# Headers_Controller.net
KiCad netlist of a schematic drawn in Altium Designer
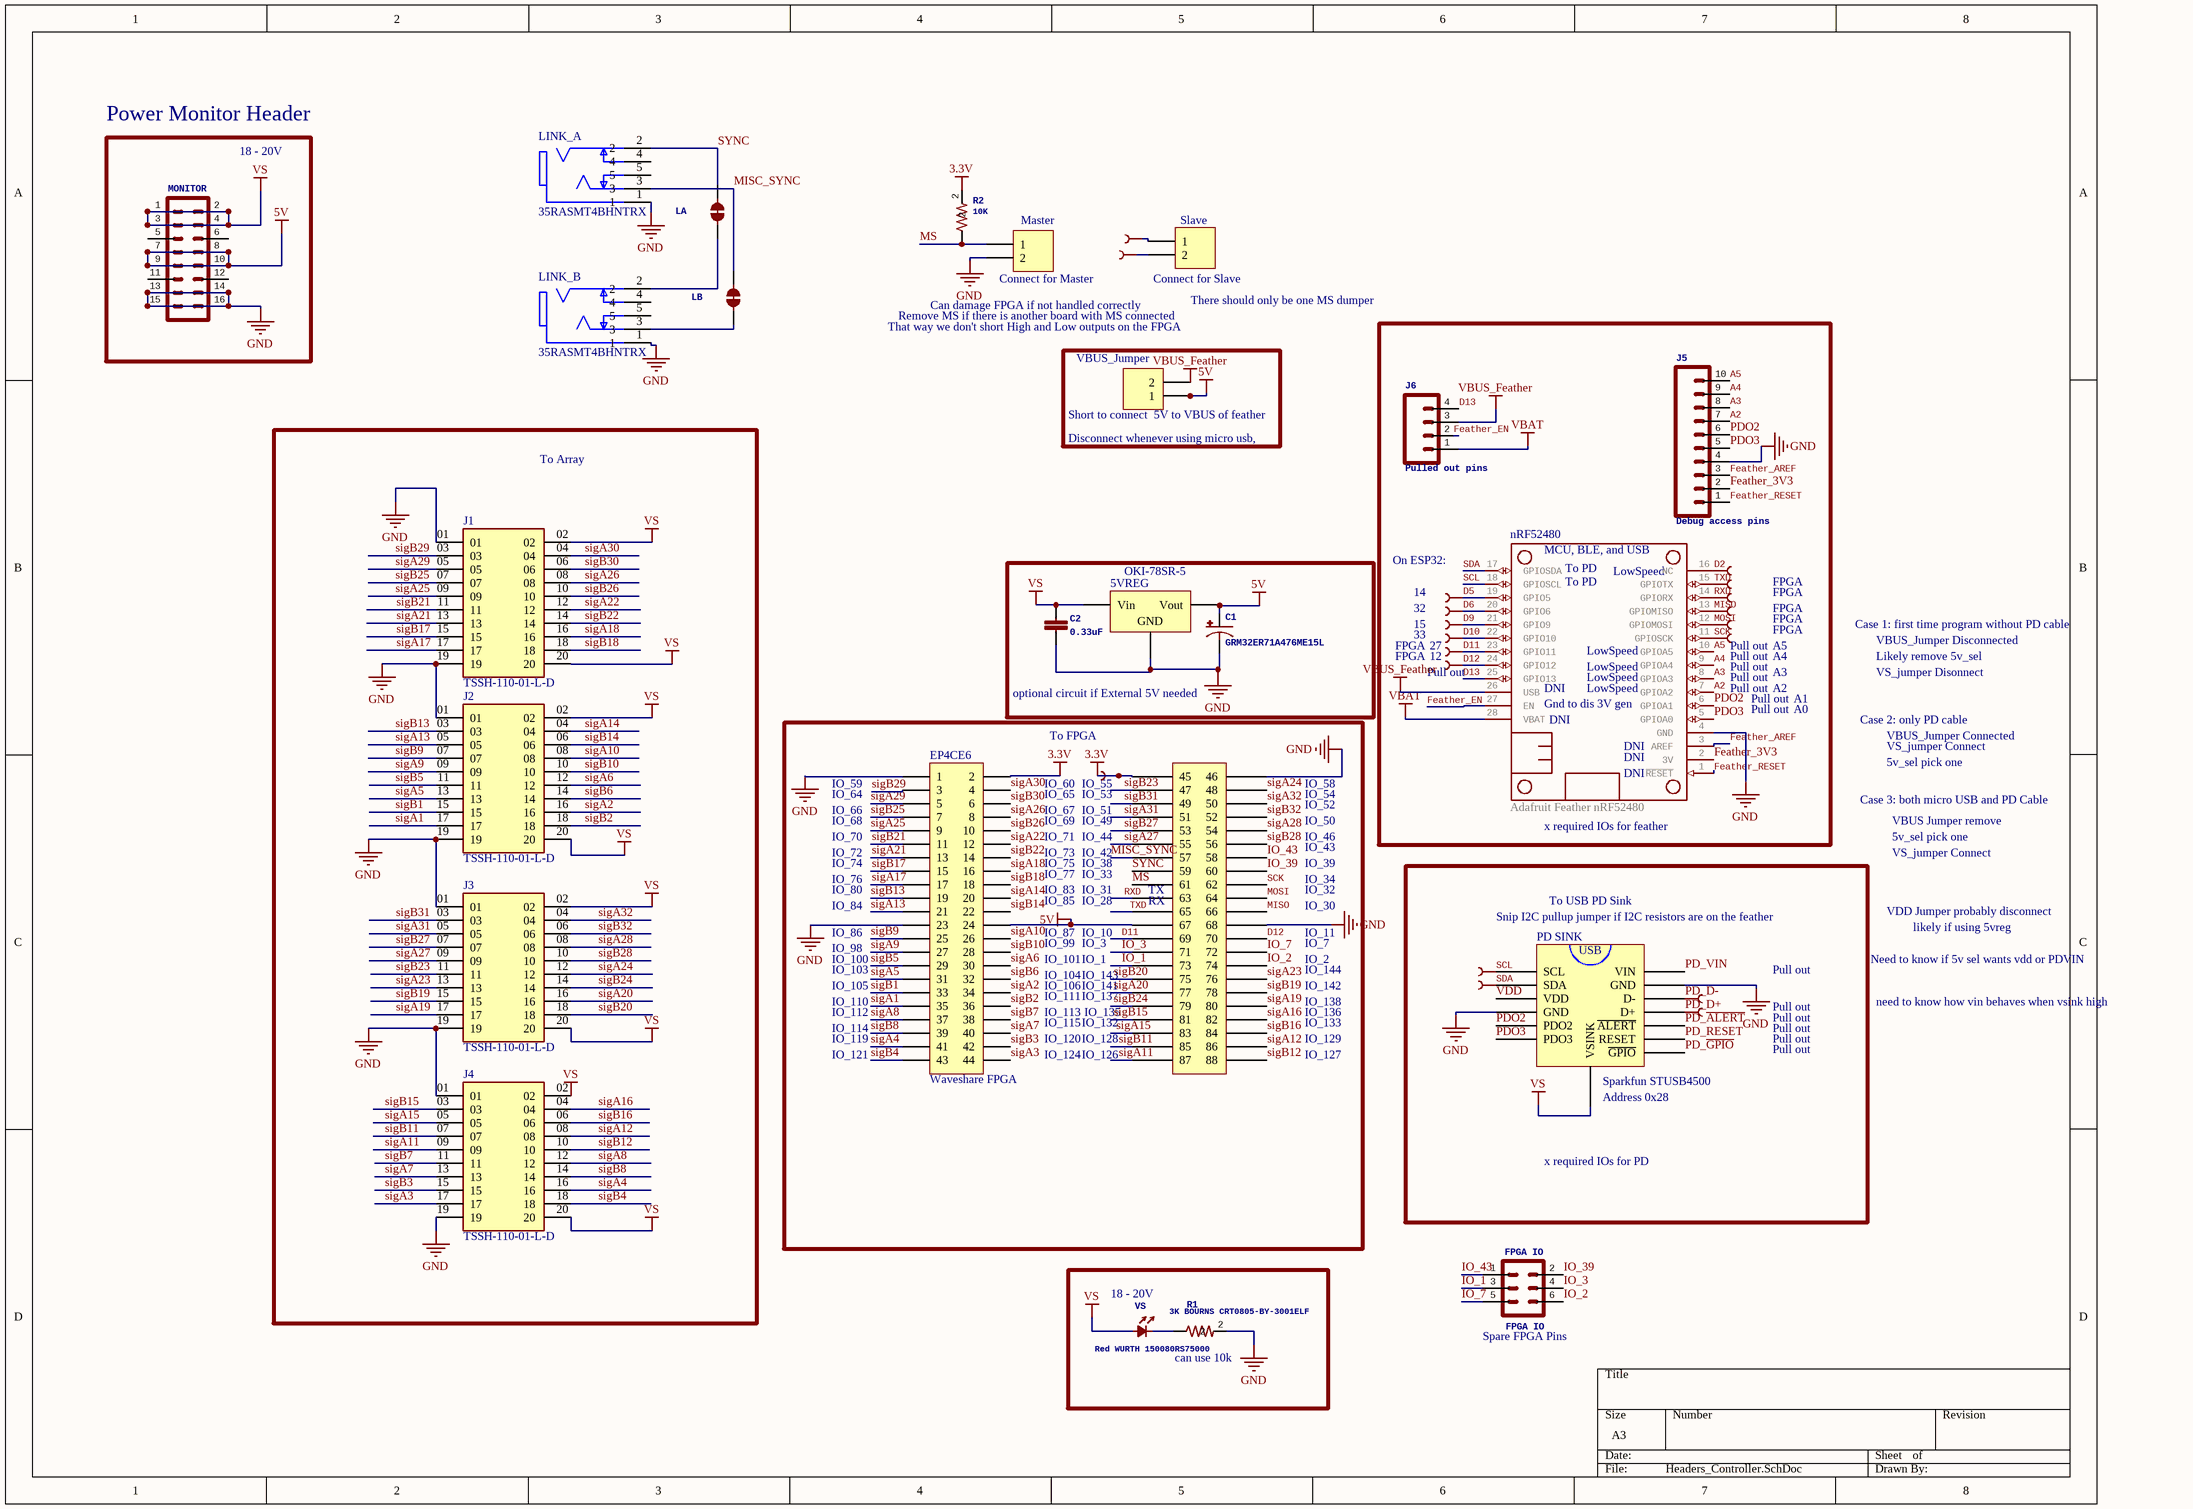
[diagram p0: Headers_Controller.SchDoc]

(export (version "E")
  (design (tool "Eeschema 10.0.6"))
  (components
    (comp (ref "3V3")
      (value "TEST-POINT3X5")
      (footprint "PAD.03X.05")
      (libsource (lib "SparkFun-Connectors") (part "TEST-POINT3X5"))
    )
    (comp (ref "5VREG")
      (value "OKI-78SR-5")
      (footprint "OOKA-78SR")
      (description "Voltage Regulator")
      (fields (field (name "PUBLISHER") "Altium Limited"))
      (libsource (lib "InteractLab") (part "Volt Reg"))
    )
    (comp (ref "C1")
      (value "GRM32ER71A476ME15L")
      (footprint "EIA6032-NOM")
      (libsource (lib "InteractLab") (part "CAP ELECTRO"))
    )
    (comp (ref "C2")
      (value "0.33uF")
      (footprint "CAP0805")
      (libsource (lib "InteractLab") (part "CAP CERAMIC"))
    )
    (comp (ref "D+")
      (value "TEST-POINT3X5")
      (footprint "PAD.03X.05")
      (libsource (lib "SparkFun-Connectors") (part "TEST-POINT3X5"))
    )
    (comp (ref "D-")
      (value "TEST-POINT3X5")
      (footprint "PAD.03X.05")
      (libsource (lib "SparkFun-Connectors") (part "TEST-POINT3X5"))
    )
    (comp (ref "D2")
      (value "TEST-POINT3X5")
      (footprint "PAD.03X.05")
      (libsource (lib "SparkFun-Connectors") (part "TEST-POINT3X5"))
    )
    (comp (ref "D5")
      (value "TEST-POINT3X5")
      (footprint "PAD.03X.05")
      (libsource (lib "SparkFun-Connectors") (part "TEST-POINT3X5"))
    )
    (comp (ref "D6")
      (value "TEST-POINT3X5")
      (footprint "PAD.03X.05")
      (libsource (lib "SparkFun-Connectors") (part "TEST-POINT3X5"))
    )
    (comp (ref "D9")
      (value "TEST-POINT3X5")
      (footprint "PAD.03X.05")
      (libsource (lib "SparkFun-Connectors") (part "TEST-POINT3X5"))
    )
    (comp (ref "D10")
      (value "TEST-POINT3X5")
      (footprint "PAD.03X.05")
      (libsource (lib "SparkFun-Connectors") (part "TEST-POINT3X5"))
    )
    (comp (ref "D11")
      (value "TEST-POINT3X5")
      (footprint "PAD.03X.05")
      (libsource (lib "SparkFun-Connectors") (part "TEST-POINT3X5"))
    )
    (comp (ref "D12")
      (value "TEST-POINT3X5")
      (footprint "PAD.03X.05")
      (libsource (lib "SparkFun-Connectors") (part "TEST-POINT3X5"))
    )
    (comp (ref "EP4CE6")
      (value "Waveshare FPGA")
      (footprint "EP4CE6 Waveshare FPGA")
      (fields (field (name "MF") "{'manufacturer': u'TE Connectivity'}") (field (name "MP") "7-534206-2"))
      (libsource (lib "InteractLab") (part "EP4CE6"))
    )
    (comp (ref "FPGA IO")
      (value "FPGA IO")
      (footprint "2X3")
      (libsource (lib "SparkFun-Connectors") (part "CONN_03X22X3_SILK_MALE_PTH"))
    )
    (comp (ref "J1")
      (value "TSSH-110-01-L-D")
      (footprint "InteractLab:SAMTEC_TSSH-110-01-L-D")
      (libsource (lib "InteractLab") (part "TSSH-110-01-L-D"))
    )
    (comp (ref "J2")
      (value "TSSH-110-01-L-D")
      (footprint "InteractLab:SAMTEC_TSSH-110-01-L-D")
      (libsource (lib "InteractLab") (part "TSSH-110-01-L-D"))
    )
    (comp (ref "J3")
      (value "TSSH-110-01-L-D")
      (footprint "InteractLab:SAMTEC_TSSH-110-01-L-D")
      (libsource (lib "InteractLab") (part "TSSH-110-01-L-D"))
    )
    (comp (ref "J4")
      (value "TSSH-110-01-L-D")
      (footprint "InteractLab:SAMTEC_TSSH-110-01-L-D")
      (libsource (lib "InteractLab") (part "TSSH-110-01-L-D"))
    )
    (comp (ref "J5")
      (value "Debug access pins")
      (footprint "1X10 _ LOCK - header")
      (libsource (lib "InteractLab") (part "CONN_10LOCK_1"))
    )
    (comp (ref "J6")
      (value "Pulled out pins")
      (footprint "1X04_LOCK - header")
      (description "Debug access pins")
      (libsource (lib "InteractLab") (part "CONN_04LOCK"))
    )
    (comp (ref "LA")
      (value "Normally closed trace jumper    This jumper has a trace between two pads so it's normally closed (NC). Use a razor knife to open the connection. For best results follow the IPC guidelines for cutting traces: Cutout at least 0.063 mm (0.005 in).  Remove all loose material to clean up the cut area.  Seal the cut with an approved epoxy.       Reapply solder to reclose the connection.")
      (footprint "SMT-JUMPER_2_NC_TRACE_SILK")
      (description "Optional disconnect")
      (libsource (lib "SparkFun-Jumpers") (part "JUMPER-SMT_2_NC_TRACE_SILK"))
    )
    (comp (ref "LB")
      (value "Normally closed trace jumper    This jumper has a trace between two pads so it's normally closed (NC). Use a razor knife to open the connection. For best results follow the IPC guidelines for cutting traces: Cutout at least 0.063 mm (0.005 in).  Remove all loose material to clean up the cut area.  Seal the cut with an approved epoxy.       Reapply solder to reclose the connection.")
      (footprint "SMT-JUMPER_2_NC_TRACE_SILK")
      (description "Optional disconnect")
      (libsource (lib "SparkFun-Jumpers") (part "JUMPER-SMT_2_NC_TRACE_SILK"))
    )
    (comp (ref "LINK_A")
      (value "35RASMT4BHNTRX")
      (footprint "SWITCHCRAFT_35RASMT4BHNTRX")
      (description "Sync port A")
      (fields (field (name "MF") "{'manufacturer': u'Switchcraft'}"))
      (libsource (lib "SnapEDA_Library") (part "35RASMT4BHNTRX"))
    )
    (comp (ref "LINK_B")
      (value "35RASMT4BHNTRX")
      (footprint "SWITCHCRAFT_35RASMT4BHNTRX")
      (description "Sync port B")
      (fields (field (name "MF") "{'manufacturer': u'Switchcraft'}"))
      (libsource (lib "SnapEDA_Library") (part "35RASMT4BHNTRX"))
    )
    (comp (ref "Master")
      (value "Connect for Master")
      (footprint "1X02_LOCK_")
      (fields (field (name "PUBLISHER") "Altium Limited"))
      (libsource (lib "") (part "Header 2_1"))
    )
    (comp (ref "MISO")
      (value "TEST-POINT3X5")
      (footprint "PAD.03X.05")
      (libsource (lib "SparkFun-Connectors") (part "TEST-POINT3X5"))
    )
    (comp (ref "MONITOR")
      (value "Access to power rails")
      (footprint "2X8")
      (libsource (lib "SparkFun-Connectors") (part "CONN_08X2_HEADER"))
    )
    (comp (ref "MOSI")
      (value "TEST-POINT3X5")
      (footprint "PAD.03X.05")
      (libsource (lib "SparkFun-Connectors") (part "TEST-POINT3X5"))
    )
    (comp (ref "nRF52480")
      (value "Adafruit Feather nRF52480")
      (footprint "Feather BLE nRF52480")
      (libsource (lib "InteractLab") (part "FEATHERWING_NODIM"))
    )
    (comp (ref "PD SINK")
      (value "Sparkfun STUSB4500")
      (footprint "Sparkfun STUSB4500")
      (description "Replace with purple board")
      (libsource (lib "InteractLab") (part "Sparkfun STUSB"))
    )
    (comp (ref "R1")
      (value "3K BOURNS CRT0805-BY-3001ELF")
      (footprint "RES-0805")
      (fields (field (name "MF") "Vishay") (field (name "MPN") "CRCW0603470RFKEA"))
      (libsource (lib "InteractLab") (part "RESISTOR"))
    )
    (comp (ref "R2")
      (value "10K")
      (footprint "RES-0805")
      (fields (field (name "MF") "Vishay") (field (name "MPN") "CRCW0603470RFKEA"))
      (libsource (lib "InteractLab") (part "RESISTOR"))
    )
    (comp (ref "RX")
      (value "TEST-POINT3X5")
      (footprint "PAD.03X.05")
      (libsource (lib "SparkFun-Connectors") (part "TEST-POINT3X5"))
    )
    (comp (ref "SCK")
      (value "TEST-POINT3X5")
      (footprint "PAD.03X.05")
      (libsource (lib "SparkFun-Connectors") (part "TEST-POINT3X5"))
    )
    (comp (ref "SCL")
      (value "TEST-POINT3X5")
      (footprint "PAD.03X.05")
      (libsource (lib "SparkFun-Connectors") (part "TEST-POINT3X5"))
    )
    (comp (ref "SDA")
      (value "TEST-POINT3X5")
      (footprint "PAD.03X.05")
      (libsource (lib "SparkFun-Connectors") (part "TEST-POINT3X5"))
    )
    (comp (ref "Slave")
      (value "Connect for Slave")
      (footprint "1X02_LOCK_")
      (description "Header, 2-Pin")
      (fields (field (name "PUBLISHER") "Altium Limited"))
      (libsource (lib "") (part "Header 2_1"))
    )
    (comp (ref "TP1")
      (value "TEST-POINT3X5")
      (footprint "PAD.03X.05")
      (libsource (lib "SparkFun-Connectors") (part "TEST-POINT3X5"))
    )
    (comp (ref "TP2")
      (value "TEST-POINT3X5")
      (footprint "PAD.03X.05")
      (libsource (lib "SparkFun-Connectors") (part "TEST-POINT3X5"))
    )
    (comp (ref "TX")
      (value "TEST-POINT3X5")
      (footprint "PAD.03X.05")
      (libsource (lib "SparkFun-Connectors") (part "TEST-POINT3X5"))
    )
    (comp (ref "VBUS_Jumper")
      (value "Short to connect  5V to VBUS of feather")
      (footprint "1X02_LOCK_")
      (description "Header, 2-Pin")
      (fields (field (name "PUBLISHER") "Altium Limited"))
      (libsource (lib "Miscellaneous Connectors") (part "Header 2"))
    )
    (comp (ref "VS")
      (value "Red WURTH 150080RS75000")
      (footprint "LED-0805 - RED")
      (libsource (lib "InteractLab") (part "LED"))
    )
  )
  (nets
    (net (code "1") (name "/A2") (class "Default")
      (node (ref "J5") (pin "7") (pinfunction "7_7") (pintype "passive"))
      (node (ref "nRF52480") (pin "7") (pinfunction "GPIOA2_7") (pintype "bidirectional"))
    )
    (net (code "2") (name "/A3") (class "Default")
      (node (ref "J5") (pin "8") (pinfunction "8_8") (pintype "passive"))
      (node (ref "nRF52480") (pin "8") (pinfunction "GPIOA3_8") (pintype "bidirectional"))
    )
    (net (code "3") (name "/A4") (class "Default")
      (node (ref "J5") (pin "9") (pinfunction "9_9") (pintype "passive"))
      (node (ref "nRF52480") (pin "9") (pinfunction "GPIOA4_9") (pintype "bidirectional"))
    )
    (net (code "4") (name "/A5") (class "Default")
      (node (ref "J5") (pin "10") (pinfunction "10_10") (pintype "passive"))
      (node (ref "nRF52480") (pin "10") (pinfunction "GPIOA5_10") (pintype "bidirectional"))
    )
    (net (code "5") (name "/D2") (class "Default")
      (node (ref "D2") (pin "P$1") (pinfunction "1_P$1") (pintype "passive"))
      (node (ref "nRF52480") (pin "16") (pinfunction "NC_16") (pintype "passive"))
    )
    (net (code "6") (name "/D5") (class "Default")
      (node (ref "D5") (pin "P$1") (pinfunction "1_P$1") (pintype "passive"))
      (node (ref "nRF52480") (pin "19") (pinfunction "GPIO5_19") (pintype "bidirectional"))
    )
    (net (code "7") (name "/D6") (class "Default")
      (node (ref "D6") (pin "P$1") (pinfunction "1_P$1") (pintype "passive"))
      (node (ref "nRF52480") (pin "20") (pinfunction "GPIO6_20") (pintype "bidirectional"))
    )
    (net (code "8") (name "/D9") (class "Default")
      (node (ref "D9") (pin "P$1") (pinfunction "1_P$1") (pintype "passive"))
      (node (ref "nRF52480") (pin "21") (pinfunction "GPIO9_21") (pintype "bidirectional"))
    )
    (net (code "9") (name "/D10") (class "Default")
      (node (ref "D10") (pin "P$1") (pinfunction "1_P$1") (pintype "passive"))
      (node (ref "nRF52480") (pin "22") (pinfunction "GPIO10_22") (pintype "bidirectional"))
    )
    (net (code "10") (name "/D11") (class "Default")
      (node (ref "D11") (pin "P$1") (pinfunction "1_P$1") (pintype "passive"))
      (node (ref "EP4CE6") (pin "69") (pinfunction "69_69") (pintype "passive"))
      (node (ref "nRF52480") (pin "23") (pinfunction "GPIO11_23") (pintype "bidirectional"))
    )
    (net (code "11") (name "/D12") (class "Default")
      (node (ref "D12") (pin "P$1") (pinfunction "1_P$1") (pintype "passive"))
      (node (ref "EP4CE6") (pin "70") (pinfunction "70_70") (pintype "passive"))
      (node (ref "nRF52480") (pin "24") (pinfunction "GPIO12_24") (pintype "bidirectional"))
    )
    (net (code "12") (name "/D13") (class "Default")
      (node (ref "J6") (pin "4") (pinfunction "4_4") (pintype "passive"))
      (node (ref "nRF52480") (pin "25") (pinfunction "GPIO13_25") (pintype "bidirectional"))
    )
    (net (code "13") (name "/Feather_3V3") (class "Default")
      (node (ref "J5") (pin "2") (pinfunction "2_2") (pintype "passive"))
      (node (ref "nRF52480") (pin "2") (pinfunction "3V_2") (pintype "power_in"))
    )
    (net (code "14") (name "/Feather_AREF") (class "Default")
      (node (ref "J5") (pin "3") (pinfunction "3_3") (pintype "passive"))
      (node (ref "nRF52480") (pin "3") (pinfunction "AREF_3") (pintype "passive"))
    )
    (net (code "15") (name "/Feather_EN") (class "Default")
      (node (ref "J6") (pin "2") (pinfunction "2_2") (pintype "passive"))
      (node (ref "nRF52480") (pin "27") (pinfunction "EN_27") (pintype "passive"))
    )
    (net (code "16") (name "/Feather_RESET") (class "Default")
      (node (ref "J5") (pin "1") (pinfunction "1_1") (pintype "passive"))
      (node (ref "nRF52480") (pin "1") (pinfunction "~{RESET}_1") (pintype "input"))
    )
    (net (code "17") (name "/IO_1") (class "Default")
      (node (ref "EP4CE6") (pin "73") (pinfunction "73_73") (pintype "passive"))
      (node (ref "FPGA IO") (pin "3") (pinfunction "3_3") (pintype "passive"))
    )
    (net (code "18") (name "/IO_2") (class "Default")
      (node (ref "EP4CE6") (pin "74") (pinfunction "74_74") (pintype "passive"))
      (node (ref "FPGA IO") (pin "6") (pinfunction "6_6") (pintype "passive"))
    )
    (net (code "19") (name "/IO_3") (class "Default")
      (node (ref "EP4CE6") (pin "71") (pinfunction "71_71") (pintype "passive"))
      (node (ref "FPGA IO") (pin "4") (pinfunction "4_4") (pintype "passive"))
    )
    (net (code "20") (name "/IO_7") (class "Default")
      (node (ref "EP4CE6") (pin "72") (pinfunction "72_72") (pintype "passive"))
      (node (ref "FPGA IO") (pin "5") (pinfunction "5_5") (pintype "passive"))
    )
    (net (code "21") (name "/IO_39") (class "Default")
      (node (ref "EP4CE6") (pin "60") (pinfunction "60_60") (pintype "passive"))
      (node (ref "FPGA IO") (pin "2") (pinfunction "2_2") (pintype "passive"))
    )
    (net (code "22") (name "/IO_43") (class "Default")
      (node (ref "EP4CE6") (pin "58") (pinfunction "58_58") (pintype "passive"))
      (node (ref "FPGA IO") (pin "1") (pinfunction "1_1") (pintype "passive"))
    )
    (net (code "23") (name "/MISC_SYNC") (class "Default")
      (node (ref "EP4CE6") (pin "57") (pinfunction "57_57") (pintype "passive"))
      (node (ref "LB") (pin "2") (pinfunction "2_2") (pintype "passive"))
      (node (ref "LINK_A") (pin "3") (pinfunction "3_3") (pintype "passive"))
    )
    (net (code "24") (name "/MISO") (class "Default")
      (node (ref "EP4CE6") (pin "66") (pinfunction "66_66") (pintype "passive"))
      (node (ref "MISO") (pin "P$1") (pinfunction "1_P$1") (pintype "passive"))
      (node (ref "nRF52480") (pin "13") (pinfunction "GPIOMISO_13") (pintype "bidirectional"))
    )
    (net (code "25") (name "/MOSI") (class "Default")
      (node (ref "EP4CE6") (pin "64") (pinfunction "64_64") (pintype "passive"))
      (node (ref "MOSI") (pin "P$1") (pinfunction "1_P$1") (pintype "passive"))
      (node (ref "nRF52480") (pin "12") (pinfunction "GPIOMOSI_12") (pintype "bidirectional"))
    )
    (net (code "26") (name "/MS") (class "Default")
      (node (ref "EP4CE6") (pin "61") (pinfunction "61_61") (pintype "passive"))
      (node (ref "Master") (pin "1") (pinfunction "1_1") (pintype "passive"))
      (node (ref "R2") (pin "1") (pinfunction "1_1") (pintype "passive"))
    )
    (net (code "27") (name "/PDO2") (class "Default")
      (node (ref "J5") (pin "6") (pinfunction "6_6") (pintype "passive"))
      (node (ref "PD SINK") (pin "5") (pinfunction "PDO2_5") (pintype "passive"))
      (node (ref "nRF52480") (pin "6") (pinfunction "GPIOA1_6") (pintype "bidirectional"))
    )
    (net (code "28") (name "/PDO3") (class "Default")
      (node (ref "J5") (pin "5") (pinfunction "5_5") (pintype "passive"))
      (node (ref "PD SINK") (pin "6") (pinfunction "PDO3_6") (pintype "passive"))
      (node (ref "nRF52480") (pin "5") (pinfunction "GPIOA0_5") (pintype "bidirectional"))
    )
    (net (code "29") (name "/PD_D+") (class "Default")
      (node (ref "D+") (pin "P$1") (pinfunction "1_P$1") (pintype "passive"))
      (node (ref "PD SINK") (pin "10") (pinfunction "D+_10") (pintype "passive"))
    )
    (net (code "30") (name "/PD_D-") (class "Default")
      (node (ref "D-") (pin "P$1") (pinfunction "1_P$1") (pintype "passive"))
      (node (ref "PD SINK") (pin "9") (pinfunction "D-_9") (pintype "passive"))
    )
    (net (code "31") (name "/PD_RESET") (class "Default")
      (node (ref "PD SINK") (pin "12") (pinfunction "RESET_12") (pintype "passive"))
    )
    (net (code "32") (name "/PD_VIN") (class "Default")
      (node (ref "PD SINK") (pin "7") (pinfunction "VIN_7") (pintype "passive"))
    )
    (net (code "33") (name "/PD_~{ALERT}") (class "Default")
      (node (ref "PD SINK") (pin "11") (pinfunction "~{ALERT}_11") (pintype "passive"))
    )
    (net (code "34") (name "/PD_~{GPIO}") (class "Default")
      (node (ref "PD SINK") (pin "13") (pinfunction "~{GPIO}_13") (pintype "passive"))
    )
    (net (code "35") (name "/RXD") (class "Default")
      (node (ref "EP4CE6") (pin "63") (pinfunction "63_63") (pintype "passive"))
      (node (ref "RX") (pin "P$1") (pinfunction "1_P$1") (pintype "passive"))
      (node (ref "nRF52480") (pin "14") (pinfunction "GPIORX_14") (pintype "bidirectional"))
    )
    (net (code "36") (name "/SCK") (class "Default")
      (node (ref "EP4CE6") (pin "62") (pinfunction "62_62") (pintype "passive"))
      (node (ref "SCK") (pin "P$1") (pinfunction "1_P$1") (pintype "passive"))
      (node (ref "nRF52480") (pin "11") (pinfunction "GPIOSCK_11") (pintype "bidirectional"))
    )
    (net (code "37") (name "/SCL") (class "Default")
      (node (ref "PD SINK") (pin "1") (pinfunction "SCL_1") (pintype "passive"))
      (node (ref "SCL") (pin "P$1") (pinfunction "1_P$1") (pintype "passive"))
      (node (ref "nRF52480") (pin "18") (pinfunction "GPIOSCL_18") (pintype "bidirectional"))
    )
    (net (code "38") (name "/SDA") (class "Default")
      (node (ref "PD SINK") (pin "2") (pinfunction "SDA_2") (pintype "passive"))
      (node (ref "SDA") (pin "P$1") (pinfunction "1_P$1") (pintype "passive"))
      (node (ref "nRF52480") (pin "17") (pinfunction "GPIOSDA_17") (pintype "bidirectional"))
    )
    (net (code "39") (name "/SYNC") (class "Default")
      (node (ref "EP4CE6") (pin "59") (pinfunction "59_59") (pintype "passive"))
      (node (ref "LA") (pin "2") (pinfunction "2_2") (pintype "passive"))
      (node (ref "LINK_A") (pin "2") (pinfunction "2_2") (pintype "passive"))
    )
    (net (code "40") (name "/TXD") (class "Default")
      (node (ref "EP4CE6") (pin "65") (pinfunction "65_65") (pintype "passive"))
      (node (ref "TX") (pin "P$1") (pinfunction "1_P$1") (pintype "passive"))
      (node (ref "nRF52480") (pin "15") (pinfunction "GPIOTX_15") (pintype "bidirectional"))
    )
    (net (code "41") (name "/VDD") (class "Default")
      (node (ref "PD SINK") (pin "3") (pinfunction "VDD_3") (pintype "passive"))
    )
    (net (code "42") (name "/sigA1") (class "Default")
      (node (ref "EP4CE6") (pin "35") (pinfunction "35_35") (pintype "passive"))
      (node (ref "J2") (pin "17") (pinfunction "17_17") (pintype "passive"))
    )
    (net (code "43") (name "/sigA2") (class "Default")
      (node (ref "EP4CE6") (pin "34") (pinfunction "34_34") (pintype "passive"))
      (node (ref "J2") (pin "16") (pinfunction "16_16") (pintype "passive"))
    )
    (net (code "44") (name "/sigA3") (class "Default")
      (node (ref "EP4CE6") (pin "44") (pinfunction "44_44") (pintype "passive"))
      (node (ref "J4") (pin "17") (pinfunction "17_17") (pintype "passive"))
    )
    (net (code "45") (name "/sigA4") (class "Default")
      (node (ref "EP4CE6") (pin "41") (pinfunction "41_41") (pintype "passive"))
      (node (ref "J4") (pin "16") (pinfunction "16_16") (pintype "passive"))
    )
    (net (code "46") (name "/sigA5") (class "Default")
      (node (ref "EP4CE6") (pin "31") (pinfunction "31_31") (pintype "passive"))
      (node (ref "J2") (pin "13") (pinfunction "13_13") (pintype "passive"))
    )
    (net (code "47") (name "/sigA6") (class "Default")
      (node (ref "EP4CE6") (pin "30") (pinfunction "30_30") (pintype "passive"))
      (node (ref "J2") (pin "12") (pinfunction "12_12") (pintype "passive"))
    )
    (net (code "48") (name "/sigA7") (class "Default")
      (node (ref "EP4CE6") (pin "40") (pinfunction "40_40") (pintype "passive"))
      (node (ref "J4") (pin "13") (pinfunction "13_13") (pintype "passive"))
    )
    (net (code "49") (name "/sigA8") (class "Default")
      (node (ref "EP4CE6") (pin "37") (pinfunction "37_37") (pintype "passive"))
      (node (ref "J4") (pin "12") (pinfunction "12_12") (pintype "passive"))
    )
    (net (code "50") (name "/sigA9") (class "Default")
      (node (ref "EP4CE6") (pin "27") (pinfunction "27_27") (pintype "passive"))
      (node (ref "J2") (pin "09") (pinfunction "09_09") (pintype "passive"))
    )
    (net (code "51") (name "/sigA10") (class "Default")
      (node (ref "EP4CE6") (pin "26") (pinfunction "26_26") (pintype "passive"))
      (node (ref "J2") (pin "08") (pinfunction "08_08") (pintype "passive"))
    )
    (net (code "52") (name "/sigA11") (class "Default")
      (node (ref "EP4CE6") (pin "87") (pinfunction "87_87") (pintype "passive"))
      (node (ref "J4") (pin "09") (pinfunction "09_09") (pintype "passive"))
    )
    (net (code "53") (name "/sigA12") (class "Default")
      (node (ref "EP4CE6") (pin "86") (pinfunction "86_86") (pintype "passive"))
      (node (ref "J4") (pin "08") (pinfunction "08_08") (pintype "passive"))
    )
    (net (code "54") (name "/sigA13") (class "Default")
      (node (ref "EP4CE6") (pin "21") (pinfunction "21_21") (pintype "passive"))
      (node (ref "J2") (pin "05") (pinfunction "05_05") (pintype "passive"))
    )
    (net (code "55") (name "/sigA14") (class "Default")
      (node (ref "EP4CE6") (pin "20") (pinfunction "20_20") (pintype "passive"))
      (node (ref "J2") (pin "04") (pinfunction "04_04") (pintype "passive"))
    )
    (net (code "56") (name "/sigA15") (class "Default")
      (node (ref "EP4CE6") (pin "83") (pinfunction "83_83") (pintype "passive"))
      (node (ref "J4") (pin "05") (pinfunction "05_05") (pintype "passive"))
    )
    (net (code "57") (name "/sigA16") (class "Default")
      (node (ref "EP4CE6") (pin "82") (pinfunction "82_82") (pintype "passive"))
      (node (ref "J4") (pin "04") (pinfunction "04_04") (pintype "passive"))
    )
    (net (code "58") (name "/sigA17") (class "Default")
      (node (ref "EP4CE6") (pin "17") (pinfunction "17_17") (pintype "passive"))
      (node (ref "J1") (pin "17") (pinfunction "17_17") (pintype "passive"))
    )
    (net (code "59") (name "/sigA18") (class "Default")
      (node (ref "EP4CE6") (pin "16") (pinfunction "16_16") (pintype "passive"))
      (node (ref "J1") (pin "16") (pinfunction "16_16") (pintype "passive"))
    )
    (net (code "60") (name "/sigA19") (class "Default")
      (node (ref "EP4CE6") (pin "80") (pinfunction "80_80") (pintype "passive"))
      (node (ref "J3") (pin "17") (pinfunction "17_17") (pintype "passive"))
    )
    (net (code "61") (name "/sigA20") (class "Default")
      (node (ref "EP4CE6") (pin "77") (pinfunction "77_77") (pintype "passive"))
      (node (ref "J3") (pin "16") (pinfunction "16_16") (pintype "passive"))
    )
    (net (code "62") (name "/sigA21") (class "Default")
      (node (ref "EP4CE6") (pin "13") (pinfunction "13_13") (pintype "passive"))
      (node (ref "J1") (pin "13") (pinfunction "13_13") (pintype "passive"))
    )
    (net (code "63") (name "/sigA22") (class "Default")
      (node (ref "EP4CE6") (pin "12") (pinfunction "12_12") (pintype "passive"))
      (node (ref "J1") (pin "12") (pinfunction "12_12") (pintype "passive"))
    )
    (net (code "64") (name "/sigA23") (class "Default")
      (node (ref "EP4CE6") (pin "76") (pinfunction "76_76") (pintype "passive"))
      (node (ref "J3") (pin "13") (pinfunction "13_13") (pintype "passive"))
    )
    (net (code "65") (name "/sigA24") (class "Default")
      (node (ref "EP4CE6") (pin "48") (pinfunction "48_48") (pintype "passive"))
      (node (ref "J3") (pin "12") (pinfunction "12_12") (pintype "passive"))
    )
    (net (code "66") (name "/sigA25") (class "Default")
      (node (ref "EP4CE6") (pin "9") (pinfunction "9_9") (pintype "passive"))
      (node (ref "J1") (pin "09") (pinfunction "09_09") (pintype "passive"))
    )
    (net (code "67") (name "/sigA26") (class "Default")
      (node (ref "EP4CE6") (pin "8") (pinfunction "8_8") (pintype "passive"))
      (node (ref "J1") (pin "08") (pinfunction "08_08") (pintype "passive"))
    )
    (net (code "68") (name "/sigA27") (class "Default")
      (node (ref "EP4CE6") (pin "55") (pinfunction "55_55") (pintype "passive"))
      (node (ref "J3") (pin "09") (pinfunction "09_09") (pintype "passive"))
    )
    (net (code "69") (name "/sigA28") (class "Default")
      (node (ref "EP4CE6") (pin "54") (pinfunction "54_54") (pintype "passive"))
      (node (ref "J3") (pin "08") (pinfunction "08_08") (pintype "passive"))
    )
    (net (code "70") (name "/sigA29") (class "Default")
      (node (ref "EP4CE6") (pin "5") (pinfunction "5_5") (pintype "passive"))
      (node (ref "J1") (pin "05") (pinfunction "05_05") (pintype "passive"))
    )
    (net (code "71") (name "/sigA30") (class "Default")
      (node (ref "EP4CE6") (pin "4") (pinfunction "4_4") (pintype "passive"))
      (node (ref "J1") (pin "04") (pinfunction "04_04") (pintype "passive"))
    )
    (net (code "72") (name "/sigA31") (class "Default")
      (node (ref "EP4CE6") (pin "51") (pinfunction "51_51") (pintype "passive"))
      (node (ref "J3") (pin "05") (pinfunction "05_05") (pintype "passive"))
    )
    (net (code "73") (name "/sigA32") (class "Default")
      (node (ref "EP4CE6") (pin "50") (pinfunction "50_50") (pintype "passive"))
      (node (ref "J3") (pin "04") (pinfunction "04_04") (pintype "passive"))
    )
    (net (code "74") (name "/sigB1") (class "Default")
      (node (ref "EP4CE6") (pin "33") (pinfunction "33_33") (pintype "passive"))
      (node (ref "J2") (pin "15") (pinfunction "15_15") (pintype "passive"))
    )
    (net (code "75") (name "/sigB2") (class "Default")
      (node (ref "EP4CE6") (pin "36") (pinfunction "36_36") (pintype "passive"))
      (node (ref "J2") (pin "18") (pinfunction "18_18") (pintype "passive"))
    )
    (net (code "76") (name "/sigB3") (class "Default")
      (node (ref "EP4CE6") (pin "42") (pinfunction "42_42") (pintype "passive"))
      (node (ref "J4") (pin "15") (pinfunction "15_15") (pintype "passive"))
    )
    (net (code "77") (name "/sigB4") (class "Default")
      (node (ref "EP4CE6") (pin "43") (pinfunction "43_43") (pintype "passive"))
      (node (ref "J4") (pin "18") (pinfunction "18_18") (pintype "passive"))
    )
    (net (code "78") (name "/sigB5") (class "Default")
      (node (ref "EP4CE6") (pin "29") (pinfunction "29_29") (pintype "passive"))
      (node (ref "J2") (pin "11") (pinfunction "11_11") (pintype "passive"))
    )
    (net (code "79") (name "/sigB6") (class "Default")
      (node (ref "EP4CE6") (pin "32") (pinfunction "32_32") (pintype "passive"))
      (node (ref "J2") (pin "14") (pinfunction "14_14") (pintype "passive"))
    )
    (net (code "80") (name "/sigB7") (class "Default")
      (node (ref "EP4CE6") (pin "38") (pinfunction "38_38") (pintype "passive"))
      (node (ref "J4") (pin "11") (pinfunction "11_11") (pintype "passive"))
    )
    (net (code "81") (name "/sigB8") (class "Default")
      (node (ref "EP4CE6") (pin "39") (pinfunction "39_39") (pintype "passive"))
      (node (ref "J4") (pin "14") (pinfunction "14_14") (pintype "passive"))
    )
    (net (code "82") (name "/sigB9") (class "Default")
      (node (ref "EP4CE6") (pin "25") (pinfunction "25_25") (pintype "passive"))
      (node (ref "J2") (pin "07") (pinfunction "07_07") (pintype "passive"))
    )
    (net (code "83") (name "/sigB10") (class "Default")
      (node (ref "EP4CE6") (pin "28") (pinfunction "28_28") (pintype "passive"))
      (node (ref "J2") (pin "10") (pinfunction "10_10") (pintype "passive"))
    )
    (net (code "84") (name "/sigB11") (class "Default")
      (node (ref "EP4CE6") (pin "85") (pinfunction "85_85") (pintype "passive"))
      (node (ref "J4") (pin "07") (pinfunction "07_07") (pintype "passive"))
    )
    (net (code "85") (name "/sigB12") (class "Default")
      (node (ref "EP4CE6") (pin "88") (pinfunction "88_88") (pintype "passive"))
      (node (ref "J4") (pin "10") (pinfunction "10_10") (pintype "passive"))
    )
    (net (code "86") (name "/sigB13") (class "Default")
      (node (ref "EP4CE6") (pin "19") (pinfunction "19_19") (pintype "passive"))
      (node (ref "J2") (pin "03") (pinfunction "03_03") (pintype "passive"))
    )
    (net (code "87") (name "/sigB14") (class "Default")
      (node (ref "EP4CE6") (pin "22") (pinfunction "22_22") (pintype "passive"))
      (node (ref "J2") (pin "06") (pinfunction "06_06") (pintype "passive"))
    )
    (net (code "88") (name "/sigB15") (class "Default")
      (node (ref "EP4CE6") (pin "81") (pinfunction "81_81") (pintype "passive"))
      (node (ref "J4") (pin "03") (pinfunction "03_03") (pintype "passive"))
    )
    (net (code "89") (name "/sigB16") (class "Default")
      (node (ref "EP4CE6") (pin "84") (pinfunction "84_84") (pintype "passive"))
      (node (ref "J4") (pin "06") (pinfunction "06_06") (pintype "passive"))
    )
    (net (code "90") (name "/sigB17") (class "Default")
      (node (ref "EP4CE6") (pin "15") (pinfunction "15_15") (pintype "passive"))
      (node (ref "J1") (pin "15") (pinfunction "15_15") (pintype "passive"))
    )
    (net (code "91") (name "/sigB18") (class "Default")
      (node (ref "EP4CE6") (pin "18") (pinfunction "18_18") (pintype "passive"))
      (node (ref "J1") (pin "18") (pinfunction "18_18") (pintype "passive"))
    )
    (net (code "92") (name "/sigB19") (class "Default")
      (node (ref "EP4CE6") (pin "78") (pinfunction "78_78") (pintype "passive"))
      (node (ref "J3") (pin "15") (pinfunction "15_15") (pintype "passive"))
    )
    (net (code "93") (name "/sigB20") (class "Default")
      (node (ref "EP4CE6") (pin "75") (pinfunction "75_75") (pintype "passive"))
      (node (ref "J3") (pin "18") (pinfunction "18_18") (pintype "passive"))
    )
    (net (code "94") (name "/sigB21") (class "Default")
      (node (ref "EP4CE6") (pin "11") (pinfunction "11_11") (pintype "passive"))
      (node (ref "J1") (pin "11") (pinfunction "11_11") (pintype "passive"))
    )
    (net (code "95") (name "/sigB22") (class "Default")
      (node (ref "EP4CE6") (pin "14") (pinfunction "14_14") (pintype "passive"))
      (node (ref "J1") (pin "14") (pinfunction "14_14") (pintype "passive"))
    )
    (net (code "96") (name "/sigB23") (class "Default")
      (node (ref "EP4CE6") (pin "47") (pinfunction "47_47") (pintype "passive"))
      (node (ref "J3") (pin "11") (pinfunction "11_11") (pintype "passive"))
    )
    (net (code "97") (name "/sigB24") (class "Default")
      (node (ref "EP4CE6") (pin "79") (pinfunction "79_79") (pintype "passive"))
      (node (ref "J3") (pin "14") (pinfunction "14_14") (pintype "passive"))
    )
    (net (code "98") (name "/sigB25") (class "Default")
      (node (ref "EP4CE6") (pin "7") (pinfunction "7_7") (pintype "passive"))
      (node (ref "J1") (pin "07") (pinfunction "07_07") (pintype "passive"))
    )
    (net (code "99") (name "/sigB26") (class "Default")
      (node (ref "EP4CE6") (pin "10") (pinfunction "10_10") (pintype "passive"))
      (node (ref "J1") (pin "10") (pinfunction "10_10") (pintype "passive"))
    )
    (net (code "100") (name "/sigB27") (class "Default")
      (node (ref "EP4CE6") (pin "53") (pinfunction "53_53") (pintype "passive"))
      (node (ref "J3") (pin "07") (pinfunction "07_07") (pintype "passive"))
    )
    (net (code "101") (name "/sigB28") (class "Default")
      (node (ref "EP4CE6") (pin "56") (pinfunction "56_56") (pintype "passive"))
      (node (ref "J3") (pin "10") (pinfunction "10_10") (pintype "passive"))
    )
    (net (code "102") (name "/sigB29") (class "Default")
      (node (ref "EP4CE6") (pin "3") (pinfunction "3_3") (pintype "passive"))
      (node (ref "J1") (pin "03") (pinfunction "03_03") (pintype "passive"))
    )
    (net (code "103") (name "/sigB30") (class "Default")
      (node (ref "EP4CE6") (pin "6") (pinfunction "6_6") (pintype "passive"))
      (node (ref "J1") (pin "06") (pinfunction "06_06") (pintype "passive"))
    )
    (net (code "104") (name "/sigB31") (class "Default")
      (node (ref "EP4CE6") (pin "49") (pinfunction "49_49") (pintype "passive"))
      (node (ref "J3") (pin "03") (pinfunction "03_03") (pintype "passive"))
    )
    (net (code "105") (name "/sigB32") (class "Default")
      (node (ref "EP4CE6") (pin "52") (pinfunction "52_52") (pintype "passive"))
      (node (ref "J3") (pin "06") (pinfunction "06_06") (pintype "passive"))
    )
    (net (code "106") (name "3.3V") (class "Default")
      (node (ref "3V3") (pin "P$1") (pinfunction "1_P$1") (pintype "passive"))
      (node (ref "EP4CE6") (pin "2") (pinfunction "2_2") (pintype "passive"))
      (node (ref "EP4CE6") (pin "45") (pinfunction "45_45") (pintype "passive"))
      (node (ref "R2") (pin "2") (pinfunction "2_2") (pintype "passive"))
    )
    (net (code "107") (name "5V") (class "Default")
      (node (ref "5VREG") (pin "OUT") (pinfunction "Vout_OUT") (pintype "passive"))
      (node (ref "C1") (pin "A") (pinfunction "A_A") (pintype "passive"))
      (node (ref "EP4CE6") (pin "24") (pinfunction "24_24") (pintype "passive"))
      (node (ref "EP4CE6") (pin "67") (pinfunction "67_67") (pintype "passive"))
      (node (ref "MONITOR") (pin "10") (pinfunction "10_10") (pintype "passive"))
      (node (ref "MONITOR") (pin "7") (pinfunction "7_7") (pintype "passive"))
      (node (ref "MONITOR") (pin "8") (pinfunction "8_8") (pintype "passive"))
      (node (ref "MONITOR") (pin "9") (pinfunction "9_9") (pintype "passive"))
      (node (ref "VBUS_Jumper") (pin "1") (pinfunction "1_1") (pintype "passive"))
    )
    (net (code "108") (name "GND") (class "Default")
      (node (ref "5VREG") (pin "GND") (pinfunction "GND_GND") (pintype "passive"))
      (node (ref "C1") (pin "C") (pinfunction "C_C") (pintype "passive"))
      (node (ref "C2") (pin "2") (pinfunction "2_2") (pintype "passive"))
      (node (ref "EP4CE6") (pin "1") (pinfunction "1_1") (pintype "passive"))
      (node (ref "EP4CE6") (pin "23") (pinfunction "23_23") (pintype "passive"))
      (node (ref "EP4CE6") (pin "46") (pinfunction "46_46") (pintype "passive"))
      (node (ref "EP4CE6") (pin "68") (pinfunction "68_68") (pintype "passive"))
      (node (ref "J1") (pin "01") (pinfunction "01_01") (pintype "passive"))
      (node (ref "J1") (pin "19") (pinfunction "19_19") (pintype "passive"))
      (node (ref "J2") (pin "01") (pinfunction "01_01") (pintype "passive"))
      (node (ref "J2") (pin "19") (pinfunction "19_19") (pintype "passive"))
      (node (ref "J3") (pin "01") (pinfunction "01_01") (pintype "passive"))
      (node (ref "J3") (pin "19") (pinfunction "19_19") (pintype "passive"))
      (node (ref "J4") (pin "01") (pinfunction "01_01") (pintype "passive"))
      (node (ref "J4") (pin "19") (pinfunction "19_19") (pintype "passive"))
      (node (ref "J5") (pin "4") (pinfunction "4_4") (pintype "passive"))
      (node (ref "LINK_A") (pin "1") (pinfunction "1_1") (pintype "passive"))
      (node (ref "LINK_B") (pin "1") (pinfunction "1_1") (pintype "passive"))
      (node (ref "MONITOR") (pin "13") (pinfunction "13_13") (pintype "passive"))
      (node (ref "MONITOR") (pin "14") (pinfunction "14_14") (pintype "passive"))
      (node (ref "MONITOR") (pin "15") (pinfunction "15_15") (pintype "passive"))
      (node (ref "MONITOR") (pin "16") (pinfunction "16_16") (pintype "passive"))
      (node (ref "Master") (pin "2") (pinfunction "2_2") (pintype "passive"))
      (node (ref "PD SINK") (pin "4") (pinfunction "GND_4") (pintype "passive"))
      (node (ref "PD SINK") (pin "8") (pinfunction "GND_8") (pintype "passive"))
      (node (ref "R1") (pin "2") (pinfunction "2_2") (pintype "passive"))
      (node (ref "nRF52480") (pin "4") (pinfunction "GND_4") (pintype "power_in"))
    )
    (net (code "109") (name "Net-(LA-Pad1)") (class "Default")
      (node (ref "LA") (pin "1") (pinfunction "1_1") (pintype "passive"))
      (node (ref "LINK_B") (pin "2") (pinfunction "2_2") (pintype "passive"))
    )
    (net (code "110") (name "Net-(LB-Pad1)") (class "Default")
      (node (ref "LB") (pin "1") (pinfunction "1_1") (pintype "passive"))
      (node (ref "LINK_B") (pin "3") (pinfunction "3_3") (pintype "passive"))
    )
    (net (code "111") (name "Net-(R1-Pad1)") (class "Default")
      (node (ref "R1") (pin "1") (pinfunction "1_1") (pintype "passive"))
      (node (ref "VS") (pin "-") (pinfunction "-_-") (pintype "passive"))
    )
    (net (code "112") (name "Net-(TP1-1)") (class "Default")
      (node (ref "Slave") (pin "1") (pinfunction "1_1") (pintype "passive"))
      (node (ref "TP1") (pin "P$1") (pinfunction "1_P$1") (pintype "passive"))
    )
    (net (code "113") (name "Net-(TP2-1)") (class "Default")
      (node (ref "Slave") (pin "2") (pinfunction "2_2") (pintype "passive"))
      (node (ref "TP2") (pin "P$1") (pinfunction "1_P$1") (pintype "passive"))
    )
    (net (code "114") (name "VBAT") (class "Default")
      (node (ref "J6") (pin "1") (pinfunction "1_1") (pintype "passive"))
      (node (ref "nRF52480") (pin "28") (pinfunction "VBAT_28") (pintype "power_in"))
    )
    (net (code "115") (name "VBUS_Feather") (class "Default")
      (node (ref "J6") (pin "3") (pinfunction "3_3") (pintype "passive"))
      (node (ref "VBUS_Jumper") (pin "2") (pinfunction "2_2") (pintype "passive"))
      (node (ref "nRF52480") (pin "26") (pinfunction "USB_26") (pintype "power_in"))
    )
    (net (code "116") (name "VS") (class "Default")
      (node (ref "5VREG") (pin "IN") (pinfunction "Vin_IN") (pintype "passive"))
      (node (ref "C2") (pin "1") (pinfunction "1_1") (pintype "passive"))
      (node (ref "J1") (pin "02") (pinfunction "02_02") (pintype "passive"))
      (node (ref "J1") (pin "20") (pinfunction "20_20") (pintype "passive"))
      (node (ref "J2") (pin "02") (pinfunction "02_02") (pintype "passive"))
      (node (ref "J2") (pin "20") (pinfunction "20_20") (pintype "passive"))
      (node (ref "J3") (pin "02") (pinfunction "02_02") (pintype "passive"))
      (node (ref "J3") (pin "20") (pinfunction "20_20") (pintype "passive"))
      (node (ref "J4") (pin "02") (pinfunction "02_02") (pintype "passive"))
      (node (ref "J4") (pin "20") (pinfunction "20_20") (pintype "passive"))
      (node (ref "MONITOR") (pin "1") (pinfunction "1_1") (pintype "passive"))
      (node (ref "MONITOR") (pin "2") (pinfunction "2_2") (pintype "passive"))
      (node (ref "MONITOR") (pin "3") (pinfunction "3_3") (pintype "passive"))
      (node (ref "MONITOR") (pin "4") (pinfunction "4_4") (pintype "passive"))
      (node (ref "PD SINK") (pin "14") (pinfunction "VSINK_14") (pintype "passive"))
      (node (ref "VS") (pin "+") (pinfunction "+_+") (pintype "passive"))
    )
    (net (code "117") (name "unconnected-(LINK_A-Pad4)") (class "Default")
      (node (ref "LINK_A") (pin "4") (pinfunction "4_4") (pintype "passive"))
    )
    (net (code "118") (name "unconnected-(LINK_A-Pad5)") (class "Default")
      (node (ref "LINK_A") (pin "5") (pinfunction "5_5") (pintype "passive"))
    )
    (net (code "119") (name "unconnected-(LINK_B-Pad4)") (class "Default")
      (node (ref "LINK_B") (pin "4") (pinfunction "4_4") (pintype "passive"))
    )
    (net (code "120") (name "unconnected-(LINK_B-Pad5)") (class "Default")
      (node (ref "LINK_B") (pin "5") (pinfunction "5_5") (pintype "passive"))
    )
    (net (code "121") (name "unconnected-(MONITOR-Pad5)") (class "Default")
      (node (ref "MONITOR") (pin "5") (pinfunction "5_5") (pintype "passive"))
    )
    (net (code "122") (name "unconnected-(MONITOR-Pad6)") (class "Default")
      (node (ref "MONITOR") (pin "6") (pinfunction "6_6") (pintype "passive"))
    )
    (net (code "123") (name "unconnected-(MONITOR-Pad11)") (class "Default")
      (node (ref "MONITOR") (pin "11") (pinfunction "11_11") (pintype "passive"))
    )
    (net (code "124") (name "unconnected-(MONITOR-Pad12)") (class "Default")
      (node (ref "MONITOR") (pin "12") (pinfunction "12_12") (pintype "passive"))
    )
  )
)
